# CH582SCH_2021-12-11.net
KiCad netlist of a schematic drawn in Altium Designer
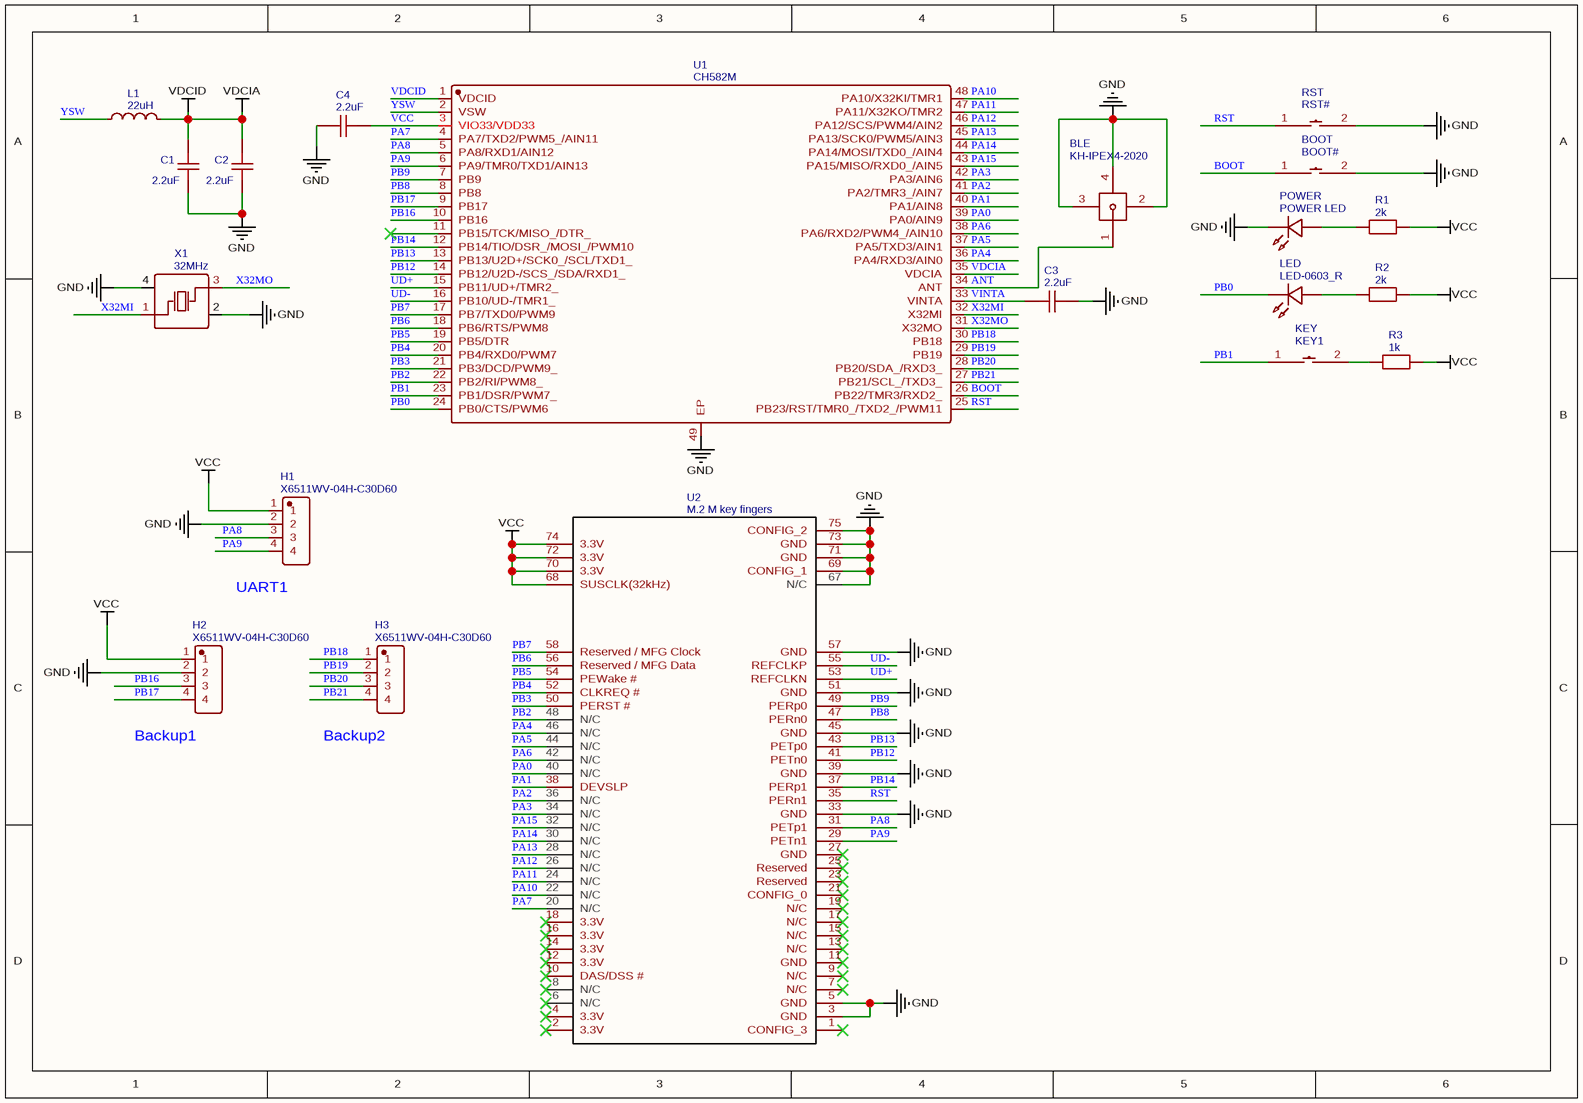
[diagram p0: CH582SCH_2021-12-11.schdoc]

(export (version "E")
  (design (tool "Eeschema 10.0.6"))
  (components
    (comp (ref "BLE")
      (value "KH-IPEX4-2020")
      (fields (field (name "BOM_SUPPLIER PART") "C530666") (field (name "CONTRIBUTOR") "LCSC"))
      (libsource (lib "altium-import") (part "root_3_KH-IPEX4-2020_"))
    )
    (comp (ref "BOOT")
      (value "BOOT#")
      (fields
        (field (name "BOM_SUPPLIER PART") "C961744")
        (field (name "BOM_MANUFACTURER PART") "K2-1807UN-A4DW-06")
        (field (name "CONTRIBUTOR") "LCSC")
      )
      (libsource (lib "altium-import") (part "root_0_BOOT#_"))
    )
    (comp (ref "C1")
      (value "2.2uF")
      (fields (field (name "CONTRIBUTOR") "LCEDA_Lib"))
      (libsource (lib "altium-import") (part "root_1_2.2uF_"))
    )
    (comp (ref "C2")
      (value "2.2uF")
      (fields (field (name "CONTRIBUTOR") "LCEDA_Lib"))
      (libsource (lib "altium-import") (part "root_1_2.2uF_"))
    )
    (comp (ref "C3")
      (value "2.2uF")
      (fields (field (name "CONTRIBUTOR") "LCEDA_Lib"))
      (libsource (lib "altium-import") (part "root_2_2.2uF_"))
    )
    (comp (ref "C4")
      (value "2.2uF")
      (fields (field (name "CONTRIBUTOR") "LCEDA_Lib"))
      (libsource (lib "altium-import") (part "root_2_2.2uF_"))
    )
    (comp (ref "H1")
      (value "X6511WV-04H-C30D60")
      (fields (field (name "BOM_SUPPLIER PART") "C706876") (field (name "CONTRIBUTOR") "LCSC"))
      (libsource (lib "altium-import") (part "root_0_X6511WV-04H-C30D60_"))
    )
    (comp (ref "H2")
      (value "X6511WV-04H-C30D60")
      (fields (field (name "BOM_SUPPLIER PART") "C706876") (field (name "CONTRIBUTOR") "LCSC"))
      (libsource (lib "altium-import") (part "root_0_X6511WV-04H-C30D60_"))
    )
    (comp (ref "H3")
      (value "X6511WV-04H-C30D60")
      (fields (field (name "BOM_SUPPLIER PART") "C706876") (field (name "CONTRIBUTOR") "LCSC"))
      (libsource (lib "altium-import") (part "root_0_X6511WV-04H-C30D60_"))
    )
    (comp (ref "KEY")
      (value "KEY1")
      (fields
        (field (name "BOM_SUPPLIER PART") "C961744")
        (field (name "BOM_MANUFACTURER PART") "K2-1807UN-A4DW-06")
        (field (name "CONTRIBUTOR") "LCSC")
      )
      (libsource (lib "altium-import") (part "root_0_KEY1_"))
    )
    (comp (ref "L1")
      (value "22uH")
      (fields (field (name "CONTRIBUTOR") "LCEDA_Lib"))
      (libsource (lib "altium-import") (part "root_0_22uH_"))
    )
    (comp (ref "LED")
      (value "LED-0603_R")
      (fields
        (field (name "BOM_MANUFACTURER PART") "19-217/R6C-AL1M2VY/3T")
        (field (name "BOM_SUPPLIER PART") "C72044")
        (field (name "CONTRIBUTOR") "LCEDA_01")
      )
      (libsource (lib "altium-import") (part "root_2_LED-0603_R_"))
    )
    (comp (ref "POWER")
      (value "POWER LED")
      (fields
        (field (name "BOM_MANUFACTURER PART") "19-217/R6C-AL1M2VY/3T")
        (field (name "BOM_SUPPLIER PART") "C72044")
        (field (name "CONTRIBUTOR") "LCEDA_01")
      )
      (libsource (lib "altium-import") (part "root_2_POWER LED_"))
    )
    (comp (ref "R1")
      (value "2k")
      (fields (field (name "CONTRIBUTOR") "LCEDA_Lib"))
      (libsource (lib "altium-import") (part "root_0_2k_"))
    )
    (comp (ref "R2")
      (value "2k")
      (fields (field (name "CONTRIBUTOR") "LCEDA_Lib"))
      (libsource (lib "altium-import") (part "root_0_2k_"))
    )
    (comp (ref "R3")
      (value "1k")
      (fields (field (name "CONTRIBUTOR") "LCEDA_Lib"))
      (libsource (lib "altium-import") (part "root_0_1k_"))
    )
    (comp (ref "RST")
      (value "RST#")
      (fields
        (field (name "BOM_SUPPLIER PART") "C961744")
        (field (name "BOM_MANUFACTURER PART") "K2-1807UN-A4DW-06")
        (field (name "CONTRIBUTOR") "LCSC")
      )
      (libsource (lib "altium-import") (part "root_0_RST#_"))
    )
    (comp (ref "U1")
      (value "CH582M")
      (fields (field (name "BOM_SUPPLIER PART") "C2920766") (field (name "CONTRIBUTOR") "LCSC"))
      (libsource (lib "altium-import") (part "root_0_CH582M_"))
    )
    (comp (ref "U2")
      (value "M.2 M key fingers")
      (fields (field (name "CONTRIBUTOR") "liuxy67"))
      (libsource (lib "altium-import") (part "root_0_M.2 M key fingers_"))
    )
    (comp (ref "X1")
      (value "32MHz")
      (fields
        (field (name "BOM_MANUFACTURER PART") "SMD-3225_4P32MHZ12PF10PPM")
        (field (name "BOM_SUPPLIER PART") "C141794")
        (field (name "CONTRIBUTOR") "LCSC")
      )
      (libsource (lib "altium-import") (part "root_0_32MHz_"))
    )
  )
  (nets
    (net (code "1") (name "/ANT") (class "Default")
      (node (ref "BLE") (pin "1") (pinfunction "1_1") (pintype "passive"))
      (node (ref "U1") (pin "34") (pinfunction "ANT_34") (pintype "passive"))
    )
    (net (code "2") (name "/BOOT") (class "Default")
      (node (ref "BOOT") (pin "1") (pinfunction "1_1") (pintype "passive"))
      (node (ref "U1") (pin "26") (pinfunction "PB22/TMR3/RXD2__26") (pintype "passive"))
    )
    (net (code "3") (name "/PA0") (class "Default")
      (node (ref "U1") (pin "39") (pinfunction "PA0/AIN9_39") (pintype "passive"))
      (node (ref "U2") (pin "40") (pinfunction "N/C_40") (pintype "passive"))
    )
    (net (code "4") (name "/PA1") (class "Default")
      (node (ref "U1") (pin "40") (pinfunction "PA1/AIN8_40") (pintype "passive"))
      (node (ref "U2") (pin "38") (pinfunction "DEVSLP_38") (pintype "passive"))
    )
    (net (code "5") (name "/PA2") (class "Default")
      (node (ref "U1") (pin "41") (pinfunction "PA2/TMR3_/AIN7_41") (pintype "passive"))
      (node (ref "U2") (pin "36") (pinfunction "N/C_36") (pintype "passive"))
    )
    (net (code "6") (name "/PA3") (class "Default")
      (node (ref "U1") (pin "42") (pinfunction "PA3/AIN6_42") (pintype "passive"))
      (node (ref "U2") (pin "34") (pinfunction "N/C_34") (pintype "passive"))
    )
    (net (code "7") (name "/PA4") (class "Default")
      (node (ref "U1") (pin "36") (pinfunction "PA4/RXD3/AIN0_36") (pintype "passive"))
      (node (ref "U2") (pin "46") (pinfunction "N/C_46") (pintype "passive"))
    )
    (net (code "8") (name "/PA5") (class "Default")
      (node (ref "U1") (pin "37") (pinfunction "PA5/TXD3/AIN1_37") (pintype "passive"))
      (node (ref "U2") (pin "44") (pinfunction "N/C_44") (pintype "passive"))
    )
    (net (code "9") (name "/PA6") (class "Default")
      (node (ref "U1") (pin "38") (pinfunction "PA6/RXD2/PWM4_/AIN10_38") (pintype "passive"))
      (node (ref "U2") (pin "42") (pinfunction "N/C_42") (pintype "passive"))
    )
    (net (code "10") (name "/PA7") (class "Default")
      (node (ref "U1") (pin "4") (pinfunction "PA7/TXD2/PWM5_/AIN11_4") (pintype "passive"))
      (node (ref "U2") (pin "20") (pinfunction "N/C_20") (pintype "passive"))
    )
    (net (code "11") (name "/PA8") (class "Default")
      (node (ref "H1") (pin "3") (pinfunction "3_3") (pintype "passive"))
      (node (ref "U1") (pin "5") (pinfunction "PA8/RXD1/AIN12_5") (pintype "passive"))
      (node (ref "U2") (pin "31") (pinfunction "PETp1_31") (pintype "passive"))
    )
    (net (code "12") (name "/PA9") (class "Default")
      (node (ref "H1") (pin "4") (pinfunction "4_4") (pintype "passive"))
      (node (ref "U1") (pin "6") (pinfunction "PA9/TMR0/TXD1/AIN13_6") (pintype "passive"))
      (node (ref "U2") (pin "29") (pinfunction "PETn1_29") (pintype "passive"))
    )
    (net (code "13") (name "/PA10") (class "Default")
      (node (ref "U1") (pin "48") (pinfunction "PA10/X32KI/TMR1_48") (pintype "passive"))
      (node (ref "U2") (pin "22") (pinfunction "N/C_22") (pintype "passive"))
    )
    (net (code "14") (name "/PA11") (class "Default")
      (node (ref "U1") (pin "47") (pinfunction "PA11/X32KO/TMR2_47") (pintype "passive"))
      (node (ref "U2") (pin "24") (pinfunction "N/C_24") (pintype "passive"))
    )
    (net (code "15") (name "/PA12") (class "Default")
      (node (ref "U1") (pin "46") (pinfunction "PA12/SCS/PWM4/AIN2_46") (pintype "passive"))
      (node (ref "U2") (pin "26") (pinfunction "N/C_26") (pintype "passive"))
    )
    (net (code "16") (name "/PA13") (class "Default")
      (node (ref "U1") (pin "45") (pinfunction "PA13/SCK0/PWM5/AIN3_45") (pintype "passive"))
      (node (ref "U2") (pin "28") (pinfunction "N/C_28") (pintype "passive"))
    )
    (net (code "17") (name "/PA14") (class "Default")
      (node (ref "U1") (pin "44") (pinfunction "PA14/MOSI/TXD0_/AIN4_44") (pintype "passive"))
      (node (ref "U2") (pin "30") (pinfunction "N/C_30") (pintype "passive"))
    )
    (net (code "18") (name "/PA15") (class "Default")
      (node (ref "U1") (pin "43") (pinfunction "PA15/MISO/RXD0_/AIN5_43") (pintype "passive"))
      (node (ref "U2") (pin "32") (pinfunction "N/C_32") (pintype "passive"))
    )
    (net (code "19") (name "/PB0") (class "Default")
      (node (ref "LED") (pin "2") (pinfunction "2_2") (pintype "passive"))
      (node (ref "U1") (pin "24") (pinfunction "PB0/CTS/PWM6_24") (pintype "passive"))
    )
    (net (code "20") (name "/PB1") (class "Default")
      (node (ref "KEY") (pin "1") (pinfunction "1_1") (pintype "passive"))
      (node (ref "U1") (pin "23") (pinfunction "PB1/DSR/PWM7__23") (pintype "passive"))
    )
    (net (code "21") (name "/PB2") (class "Default")
      (node (ref "U1") (pin "22") (pinfunction "PB2/RI/PWM8__22") (pintype "passive"))
      (node (ref "U2") (pin "48") (pinfunction "N/C_48") (pintype "passive"))
    )
    (net (code "22") (name "/PB3") (class "Default")
      (node (ref "U1") (pin "21") (pinfunction "PB3/DCD/PWM9__21") (pintype "passive"))
      (node (ref "U2") (pin "50") (pinfunction "PERST_#_50") (pintype "passive"))
    )
    (net (code "23") (name "/PB4") (class "Default")
      (node (ref "U1") (pin "20") (pinfunction "PB4/RXD0/PWM7_20") (pintype "passive"))
      (node (ref "U2") (pin "52") (pinfunction "CLKREQ_#_52") (pintype "passive"))
    )
    (net (code "24") (name "/PB5") (class "Default")
      (node (ref "U1") (pin "19") (pinfunction "PB5/DTR_19") (pintype "passive"))
      (node (ref "U2") (pin "54") (pinfunction "PEWake_#_54") (pintype "passive"))
    )
    (net (code "25") (name "/PB6") (class "Default")
      (node (ref "U1") (pin "18") (pinfunction "PB6/RTS/PWM8_18") (pintype "passive"))
      (node (ref "U2") (pin "56") (pinfunction "Reserved_/_MFG_Data_56") (pintype "passive"))
    )
    (net (code "26") (name "/PB7") (class "Default")
      (node (ref "U1") (pin "17") (pinfunction "PB7/TXD0/PWM9_17") (pintype "passive"))
      (node (ref "U2") (pin "58") (pinfunction "Reserved_/_MFG_Clock_58") (pintype "passive"))
    )
    (net (code "27") (name "/PB8") (class "Default")
      (node (ref "U1") (pin "8") (pinfunction "PB8_8") (pintype "passive"))
      (node (ref "U2") (pin "47") (pinfunction "PERn0_47") (pintype "passive"))
    )
    (net (code "28") (name "/PB9") (class "Default")
      (node (ref "U1") (pin "7") (pinfunction "PB9_7") (pintype "passive"))
      (node (ref "U2") (pin "49") (pinfunction "PERp0_49") (pintype "passive"))
    )
    (net (code "29") (name "/PB12") (class "Default")
      (node (ref "U1") (pin "14") (pinfunction "PB12/U2D-/SCS_/SDA/RXD1__14") (pintype "passive"))
      (node (ref "U2") (pin "41") (pinfunction "PETn0_41") (pintype "passive"))
    )
    (net (code "30") (name "/PB13") (class "Default")
      (node (ref "U1") (pin "13") (pinfunction "PB13/U2D+/SCK0_/SCL/TXD1__13") (pintype "passive"))
      (node (ref "U2") (pin "43") (pinfunction "PETp0_43") (pintype "passive"))
    )
    (net (code "31") (name "/PB14") (class "Default")
      (node (ref "U1") (pin "12") (pinfunction "PB14/TIO/DSR_/MOSI_/PWM10_12") (pintype "passive"))
      (node (ref "U2") (pin "37") (pinfunction "PERp1_37") (pintype "passive"))
    )
    (net (code "32") (name "/PB16") (class "Default")
      (node (ref "H2") (pin "3") (pinfunction "3_3") (pintype "passive"))
      (node (ref "U1") (pin "10") (pinfunction "PB16_10") (pintype "passive"))
    )
    (net (code "33") (name "/PB17") (class "Default")
      (node (ref "H2") (pin "4") (pinfunction "4_4") (pintype "passive"))
      (node (ref "U1") (pin "9") (pinfunction "PB17_9") (pintype "passive"))
    )
    (net (code "34") (name "/PB18") (class "Default")
      (node (ref "H3") (pin "1") (pinfunction "1_1") (pintype "passive"))
      (node (ref "U1") (pin "30") (pinfunction "PB18_30") (pintype "passive"))
    )
    (net (code "35") (name "/PB19") (class "Default")
      (node (ref "H3") (pin "2") (pinfunction "2_2") (pintype "passive"))
      (node (ref "U1") (pin "29") (pinfunction "PB19_29") (pintype "passive"))
    )
    (net (code "36") (name "/PB20") (class "Default")
      (node (ref "H3") (pin "3") (pinfunction "3_3") (pintype "passive"))
      (node (ref "U1") (pin "28") (pinfunction "PB20/SDA_/RXD3__28") (pintype "passive"))
    )
    (net (code "37") (name "/PB21") (class "Default")
      (node (ref "H3") (pin "4") (pinfunction "4_4") (pintype "passive"))
      (node (ref "U1") (pin "27") (pinfunction "PB21/SCL_/TXD3__27") (pintype "passive"))
    )
    (net (code "38") (name "/RST") (class "Default")
      (node (ref "RST") (pin "1") (pinfunction "1_1") (pintype "passive"))
      (node (ref "U1") (pin "25") (pinfunction "PB23/RST/TMR0_/TXD2_/PWM11_25") (pintype "passive"))
      (node (ref "U2") (pin "35") (pinfunction "PERn1_35") (pintype "passive"))
    )
    (net (code "39") (name "/UD+") (class "Default")
      (node (ref "U1") (pin "15") (pinfunction "PB11/UD+/TMR2__15") (pintype "passive"))
      (node (ref "U2") (pin "53") (pinfunction "REFCLKN_53") (pintype "passive"))
    )
    (net (code "40") (name "/UD-") (class "Default")
      (node (ref "U1") (pin "16") (pinfunction "PB10/UD-/TMR1__16") (pintype "passive"))
      (node (ref "U2") (pin "55") (pinfunction "REFCLKP_55") (pintype "passive"))
    )
    (net (code "41") (name "/VINTA") (class "Default")
      (node (ref "C3") (pin "2") (pinfunction "2_2") (pintype "passive"))
      (node (ref "U1") (pin "33") (pinfunction "VINTA_33") (pintype "passive"))
    )
    (net (code "42") (name "/X32MI") (class "Default")
      (node (ref "U1") (pin "32") (pinfunction "X32MI_32") (pintype "passive"))
      (node (ref "X1") (pin "1") (pinfunction "OSC1_1") (pintype "passive"))
    )
    (net (code "43") (name "/X32MO") (class "Default")
      (node (ref "U1") (pin "31") (pinfunction "X32MO_31") (pintype "passive"))
      (node (ref "X1") (pin "3") (pinfunction "OSC2_3") (pintype "passive"))
    )
    (net (code "44") (name "/YSW") (class "Default")
      (node (ref "L1") (pin "1") (pinfunction "1_1") (pintype "passive"))
      (node (ref "U1") (pin "2") (pinfunction "VSW_2") (pintype "passive"))
    )
    (net (code "45") (name "GND") (class "Default")
      (node (ref "BLE") (pin "2") (pinfunction "2_2") (pintype "passive"))
      (node (ref "BLE") (pin "3") (pinfunction "3_3") (pintype "passive"))
      (node (ref "BLE") (pin "4") (pinfunction "4_4") (pintype "passive"))
      (node (ref "BOOT") (pin "2") (pinfunction "2_2") (pintype "passive"))
      (node (ref "C1") (pin "1") (pinfunction "1_1") (pintype "passive"))
      (node (ref "C2") (pin "1") (pinfunction "1_1") (pintype "passive"))
      (node (ref "C3") (pin "1") (pinfunction "1_1") (pintype "passive"))
      (node (ref "C4") (pin "2") (pinfunction "2_2") (pintype "passive"))
      (node (ref "H1") (pin "2") (pinfunction "2_2") (pintype "passive"))
      (node (ref "H2") (pin "2") (pinfunction "2_2") (pintype "passive"))
      (node (ref "POWER") (pin "2") (pinfunction "2_2") (pintype "passive"))
      (node (ref "RST") (pin "2") (pinfunction "2_2") (pintype "passive"))
      (node (ref "U1") (pin "49") (pinfunction "EP_49") (pintype "passive"))
      (node (ref "U2") (pin "3") (pinfunction "GND_3") (pintype "passive"))
      (node (ref "U2") (pin "33") (pinfunction "GND_33") (pintype "passive"))
      (node (ref "U2") (pin "39") (pinfunction "GND_39") (pintype "passive"))
      (node (ref "U2") (pin "45") (pinfunction "GND_45") (pintype "passive"))
      (node (ref "U2") (pin "5") (pinfunction "GND_5") (pintype "passive"))
      (node (ref "U2") (pin "51") (pinfunction "GND_51") (pintype "passive"))
      (node (ref "U2") (pin "57") (pinfunction "GND_57") (pintype "passive"))
      (node (ref "U2") (pin "67") (pinfunction "N/C_67") (pintype "passive"))
      (node (ref "U2") (pin "69") (pinfunction "CONFIG_1_69") (pintype "passive"))
      (node (ref "U2") (pin "71") (pinfunction "GND_71") (pintype "passive"))
      (node (ref "U2") (pin "73") (pinfunction "GND_73") (pintype "passive"))
      (node (ref "U2") (pin "75") (pinfunction "CONFIG_2_75") (pintype "passive"))
      (node (ref "X1") (pin "2") (pinfunction "GND_2") (pintype "passive"))
      (node (ref "X1") (pin "4") (pinfunction "GND_4") (pintype "passive"))
    )
    (net (code "46") (name "Net-(KEY-Pad2)") (class "Default")
      (node (ref "KEY") (pin "2") (pinfunction "2_2") (pintype "passive"))
      (node (ref "R3") (pin "1") (pinfunction "1_1") (pintype "passive"))
    )
    (net (code "47") (name "Net-(LED-Pad1)") (class "Default")
      (node (ref "LED") (pin "1") (pinfunction "1_1") (pintype "passive"))
      (node (ref "R2") (pin "1") (pinfunction "1_1") (pintype "passive"))
    )
    (net (code "48") (name "Net-(POWER-Pad1)") (class "Default")
      (node (ref "POWER") (pin "1") (pinfunction "1_1") (pintype "passive"))
      (node (ref "R1") (pin "1") (pinfunction "1_1") (pintype "passive"))
    )
    (net (code "49") (name "VCC") (class "Default")
      (node (ref "C4") (pin "1") (pinfunction "1_1") (pintype "passive"))
      (node (ref "H1") (pin "1") (pinfunction "1_1") (pintype "passive"))
      (node (ref "H2") (pin "1") (pinfunction "1_1") (pintype "passive"))
      (node (ref "R1") (pin "2") (pinfunction "2_2") (pintype "passive"))
      (node (ref "R2") (pin "2") (pinfunction "2_2") (pintype "passive"))
      (node (ref "R3") (pin "2") (pinfunction "2_2") (pintype "passive"))
      (node (ref "U1") (pin "3") (pinfunction "VIO33/VDD33_3") (pintype "passive"))
      (node (ref "U2") (pin "68") (pinfunction "SUSCLK(32kHz)_68") (pintype "passive"))
      (node (ref "U2") (pin "70") (pinfunction "3.3V_70") (pintype "passive"))
      (node (ref "U2") (pin "72") (pinfunction "3.3V_72") (pintype "passive"))
      (node (ref "U2") (pin "74") (pinfunction "3.3V_74") (pintype "passive"))
    )
    (net (code "50") (name "VDCIA") (class "Default")
      (node (ref "C1") (pin "2") (pinfunction "2_2") (pintype "passive"))
      (node (ref "C2") (pin "2") (pinfunction "2_2") (pintype "passive"))
      (node (ref "L1") (pin "2") (pinfunction "2_2") (pintype "passive"))
      (node (ref "U1") (pin "1") (pinfunction "VDCID_1") (pintype "passive"))
      (node (ref "U1") (pin "35") (pinfunction "VDCIA_35") (pintype "passive"))
    )
    (net (code "51") (name "unconnected-(U1-PB15{slash}TCK{slash}MISO_{slash}DTR_-Pad11)") (class "Default")
      (node (ref "U1") (pin "11") (pinfunction "PB15/TCK/MISO_/DTR__11") (pintype "passive+no_connect"))
    )
    (net (code "52") (name "unconnected-(U2-3.3V-Pad2)") (class "Default")
      (node (ref "U2") (pin "2") (pinfunction "3.3V_2") (pintype "passive+no_connect"))
    )
    (net (code "53") (name "unconnected-(U2-3.3V-Pad4)") (class "Default")
      (node (ref "U2") (pin "4") (pinfunction "3.3V_4") (pintype "passive+no_connect"))
    )
    (net (code "54") (name "unconnected-(U2-3.3V-Pad12)") (class "Default")
      (node (ref "U2") (pin "12") (pinfunction "3.3V_12") (pintype "passive+no_connect"))
    )
    (net (code "55") (name "unconnected-(U2-3.3V-Pad14)") (class "Default")
      (node (ref "U2") (pin "14") (pinfunction "3.3V_14") (pintype "passive+no_connect"))
    )
    (net (code "56") (name "unconnected-(U2-3.3V-Pad16)") (class "Default")
      (node (ref "U2") (pin "16") (pinfunction "3.3V_16") (pintype "passive+no_connect"))
    )
    (net (code "57") (name "unconnected-(U2-3.3V-Pad18)") (class "Default")
      (node (ref "U2") (pin "18") (pinfunction "3.3V_18") (pintype "passive+no_connect"))
    )
    (net (code "58") (name "unconnected-(U2-CONFIG_0-Pad21)") (class "Default")
      (node (ref "U2") (pin "21") (pinfunction "CONFIG_0_21") (pintype "passive+no_connect"))
    )
    (net (code "59") (name "unconnected-(U2-CONFIG_3-Pad1)") (class "Default")
      (node (ref "U2") (pin "1") (pinfunction "CONFIG_3_1") (pintype "passive+no_connect"))
    )
    (net (code "60") (name "unconnected-(U2-DAS{slash}DSS_#-Pad10)") (class "Default")
      (node (ref "U2") (pin "10") (pinfunction "DAS/DSS_#_10") (pintype "passive+no_connect"))
    )
    (net (code "61") (name "unconnected-(U2-GND-Pad11)") (class "Default")
      (node (ref "U2") (pin "11") (pinfunction "GND_11") (pintype "passive+no_connect"))
    )
    (net (code "62") (name "unconnected-(U2-GND-Pad27)") (class "Default")
      (node (ref "U2") (pin "27") (pinfunction "GND_27") (pintype "passive+no_connect"))
    )
    (net (code "63") (name "unconnected-(U2-N{slash}C-Pad6)") (class "Default")
      (node (ref "U2") (pin "6") (pinfunction "N/C_6") (pintype "passive+no_connect"))
    )
    (net (code "64") (name "unconnected-(U2-N{slash}C-Pad7)") (class "Default")
      (node (ref "U2") (pin "7") (pinfunction "N/C_7") (pintype "passive+no_connect"))
    )
    (net (code "65") (name "unconnected-(U2-N{slash}C-Pad8)") (class "Default")
      (node (ref "U2") (pin "8") (pinfunction "N/C_8") (pintype "passive+no_connect"))
    )
    (net (code "66") (name "unconnected-(U2-N{slash}C-Pad9)") (class "Default")
      (node (ref "U2") (pin "9") (pinfunction "N/C_9") (pintype "passive+no_connect"))
    )
    (net (code "67") (name "unconnected-(U2-N{slash}C-Pad13)") (class "Default")
      (node (ref "U2") (pin "13") (pinfunction "N/C_13") (pintype "passive+no_connect"))
    )
    (net (code "68") (name "unconnected-(U2-N{slash}C-Pad15)") (class "Default")
      (node (ref "U2") (pin "15") (pinfunction "N/C_15") (pintype "passive+no_connect"))
    )
    (net (code "69") (name "unconnected-(U2-N{slash}C-Pad17)") (class "Default")
      (node (ref "U2") (pin "17") (pinfunction "N/C_17") (pintype "passive+no_connect"))
    )
    (net (code "70") (name "unconnected-(U2-N{slash}C-Pad19)") (class "Default")
      (node (ref "U2") (pin "19") (pinfunction "N/C_19") (pintype "passive+no_connect"))
    )
    (net (code "71") (name "unconnected-(U2-Reserved-Pad23)") (class "Default")
      (node (ref "U2") (pin "23") (pinfunction "Reserved_23") (pintype "passive+no_connect"))
    )
    (net (code "72") (name "unconnected-(U2-Reserved-Pad25)") (class "Default")
      (node (ref "U2") (pin "25") (pinfunction "Reserved_25") (pintype "passive+no_connect"))
    )
  )
)
